# SparkFun_9DoF_ISM330DHCX-MMC5983MA.net
KiCad netlist of a schematic drawn in EAGLE
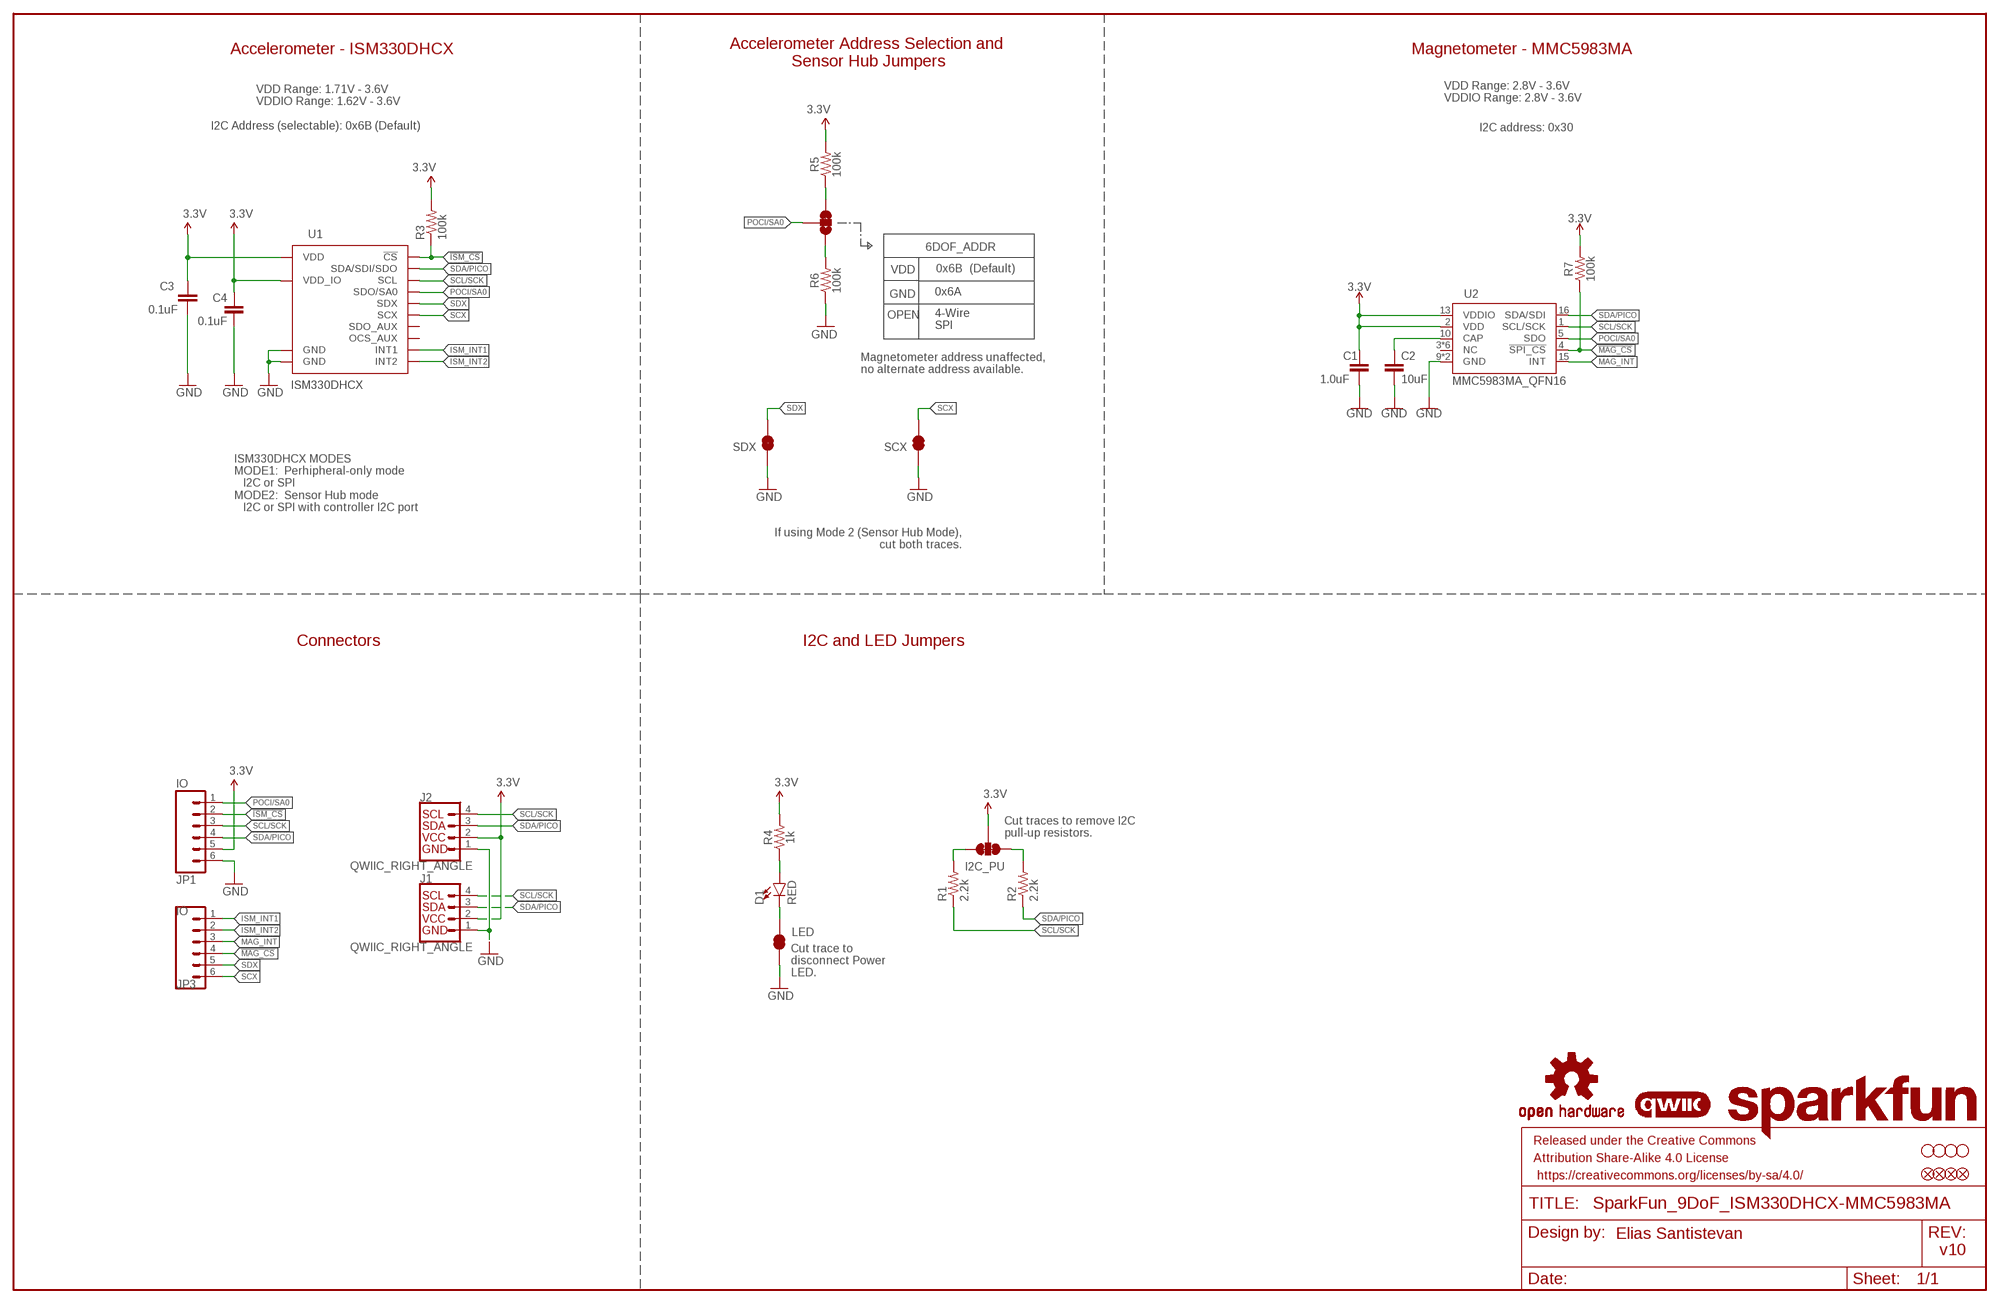
[diagram p0: schematic, sheet 1]

(export (version "E")
  (design (tool "Eeschema 10.0.6"))
  (components
    (comp (ref "6DOF_ADDR")
      (value "JUMPER-SMT_3_1-NC_TRACE_SILK")
      (footprint "eagle-import:SMT-JUMPER_3_1-NC_TRACE_SILK")
      (libsource (lib "eagle-import") (part "JUMPER-SMT_3_1-NC_TRACE_SILK"))
    )
    (comp (ref "C1")
      (value "1.0uF")
      (footprint "eagle-import:0603")
      (libsource (lib "eagle-import") (part "1.0UF-0603-16V-10%"))
    )
    (comp (ref "C2")
      (value "10uF")
      (footprint "eagle-import:0603")
      (libsource (lib "eagle-import") (part "10UF-0603-6.3V-20%"))
    )
    (comp (ref "C3")
      (value "0.1uF")
      (footprint "eagle-import:0603")
      (libsource (lib "eagle-import") (part "0.1UF-0603-25V-(+80/-20%)"))
    )
    (comp (ref "C4")
      (value "0.1uF")
      (footprint "eagle-import:0603")
      (libsource (lib "eagle-import") (part "0.1UF-0603-25V-(+80/-20%)"))
    )
    (comp (ref "D1")
      (value "RED")
      (footprint "eagle-import:LED-0603")
      (libsource (lib "eagle-import") (part "LED-RED0603"))
    )
    (comp (ref "FD1")
      (value "FIDUCIALUFIDUCIAL")
      (footprint "eagle-import:FIDUCIAL-MICRO")
      (libsource (lib "eagle-import") (part "FIDUCIALUFIDUCIAL"))
    )
    (comp (ref "FD2")
      (value "FIDUCIALUFIDUCIAL")
      (footprint "eagle-import:FIDUCIAL-MICRO")
      (libsource (lib "eagle-import") (part "FIDUCIALUFIDUCIAL"))
    )
    (comp (ref "FID1")
      (value "FIDUCIALUFIDUCIAL")
      (footprint "eagle-import:FIDUCIAL-MICRO")
      (libsource (lib "eagle-import") (part "FIDUCIALUFIDUCIAL"))
    )
    (comp (ref "FID2")
      (value "FIDUCIALUFIDUCIAL")
      (footprint "eagle-import:FIDUCIAL-MICRO")
      (libsource (lib "eagle-import") (part "FIDUCIALUFIDUCIAL"))
    )
    (comp (ref "FRAME2")
      (value "FRAME-LEDGER")
      (footprint "eagle-import:CREATIVE_COMMONS")
      (libsource (lib "eagle-import") (part "FRAME-LEDGER"))
    )
    (comp (ref "I2C_PU")
      (value "S_MODE")
      (footprint "eagle-import:SMT-JUMPER_3_2-NC_TRACE_SILK")
      (libsource (lib "eagle-import") (part "JUMPER-SMT_3_2-NC_TRACE_SILK"))
    )
    (comp (ref "J1")
      (value "QWIIC_RIGHT_ANGLE")
      (footprint "eagle-import:JST04_1MM_RA")
      (libsource (lib "eagle-import") (part "QWIIC_CONNECTORJS-1MM"))
    )
    (comp (ref "J2")
      (value "QWIIC_RIGHT_ANGLE")
      (footprint "eagle-import:JST04_1MM_RA")
      (libsource (lib "eagle-import") (part "QWIIC_CONNECTORJS-1MM"))
    )
    (comp (ref "JP1")
      (value "IO")
      (footprint "eagle-import:1X06_NO_SILK")
      (libsource (lib "eagle-import") (part "CONN_06NO_SILK_NO_POP"))
    )
    (comp (ref "JP3")
      (value "IO")
      (footprint "eagle-import:1X06_NO_SILK")
      (libsource (lib "eagle-import") (part "CONN_06NO_SILK_NO_POP"))
    )
    (comp (ref "LED")
      (value "JUMPER-SMT_2_NC_TRACE_SILK")
      (footprint "eagle-import:SMT-JUMPER_2_NC_TRACE_SILK")
      (libsource (lib "eagle-import") (part "JUMPER-SMT_2_NC_TRACE_SILK"))
    )
    (comp (ref "LOGO1")
      (value "QWIIC_LOGO_4MM")
      (footprint "eagle-import:QWIIC_4MM")
      (libsource (lib "eagle-import") (part "QWIIC_LOGO_4MM"))
    )
    (comp (ref "LOGO2")
      (value "OSHW-LOGOMINI")
      (footprint "eagle-import:OSHW-LOGO-MINI")
      (libsource (lib "eagle-import") (part "OSHW-LOGOMINI"))
    )
    (comp (ref "LOGO3")
      (value "SFE_LOGO_NAME.1_INCH")
      (footprint "eagle-import:SFE_LOGO_NAME_.1")
      (libsource (lib "eagle-import") (part "SFE_LOGO_NAME.1_INCH"))
    )
    (comp (ref "R1")
      (value "2.2k")
      (footprint "eagle-import:0603")
      (libsource (lib "eagle-import") (part "2.2KOHM-0603-1/10W-1%"))
    )
    (comp (ref "R2")
      (value "2.2k")
      (footprint "eagle-import:0603")
      (libsource (lib "eagle-import") (part "2.2KOHM-0603-1/10W-1%"))
    )
    (comp (ref "R3")
      (value "100k")
      (footprint "eagle-import:0603")
      (libsource (lib "eagle-import") (part "100KOHM-0603-1/10W-1%"))
    )
    (comp (ref "R4")
      (value "1k")
      (footprint "eagle-import:0603")
      (libsource (lib "eagle-import") (part "1KOHM-0603-1/10W-1%"))
    )
    (comp (ref "R5")
      (value "100k")
      (footprint "eagle-import:0603")
      (libsource (lib "eagle-import") (part "100KOHM-0603-1/10W-1%"))
    )
    (comp (ref "R6")
      (value "100k")
      (footprint "eagle-import:0603")
      (libsource (lib "eagle-import") (part "100KOHM-0603-1/10W-1%"))
    )
    (comp (ref "R7")
      (value "100k")
      (footprint "eagle-import:0603")
      (libsource (lib "eagle-import") (part "100KOHM-0603-1/10W-1%"))
    )
    (comp (ref "SCX")
      (value "JUMPER-SMT_2_NC_TRACE_SILK")
      (footprint "eagle-import:SMT-JUMPER_2_NC_TRACE_SILK")
      (libsource (lib "eagle-import") (part "JUMPER-SMT_2_NC_TRACE_SILK"))
    )
    (comp (ref "SDX")
      (value "JUMPER-SMT_2_NC_TRACE_SILK")
      (footprint "eagle-import:SMT-JUMPER_2_NC_TRACE_SILK")
      (libsource (lib "eagle-import") (part "JUMPER-SMT_2_NC_TRACE_SILK"))
    )
    (comp (ref "STANDOFF1")
      (value "STAND-OFFTIGHT")
      (footprint "eagle-import:STAND-OFF-TIGHT")
      (libsource (lib "eagle-import") (part "STAND-OFFTIGHT"))
    )
    (comp (ref "STANDOFF2")
      (value "STAND-OFFTIGHT")
      (footprint "eagle-import:STAND-OFF-TIGHT")
      (libsource (lib "eagle-import") (part "STAND-OFFTIGHT"))
    )
    (comp (ref "STANDOFF3")
      (value "STAND-OFFTIGHT")
      (footprint "eagle-import:STAND-OFF-TIGHT")
      (libsource (lib "eagle-import") (part "STAND-OFFTIGHT"))
    )
    (comp (ref "STANDOFF4")
      (value "STAND-OFFTIGHT")
      (footprint "eagle-import:STAND-OFF-TIGHT")
      (libsource (lib "eagle-import") (part "STAND-OFFTIGHT"))
    )
    (comp (ref "U1")
      (value "ISM330DHCX")
      (footprint "eagle-import:LGA-14L")
      (libsource (lib "eagle-import") (part "ISM330DHCX"))
    )
    (comp (ref "U2")
      (value "MMC5983MA_QFN16")
      (footprint "eagle-import:LGA-16-3X3MM-4X4PINS")
      (libsource (lib "eagle-import") (part "MMC5983MA_QFN16"))
    )
  )
  (nets
    (net (code "1") (name "/~{ISM_CS}") (class "Default")
      (node (ref "JP1") (pin "2") (pinfunction "2_2") (pintype "passive"))
      (node (ref "R3") (pin "1") (pinfunction "1_1") (pintype "passive"))
      (node (ref "U1") (pin "P12") (pinfunction "~{CS}_P12") (pintype "bidirectional"))
    )
    (net (code "2") (name "/~{MAG_CS}") (class "Default")
      (node (ref "JP3") (pin "4") (pinfunction "4_4") (pintype "passive"))
      (node (ref "R7") (pin "1") (pinfunction "1_1") (pintype "passive"))
      (node (ref "U2") (pin "4") (pinfunction "~{SPI_CS}_4") (pintype "input"))
    )
    (net (code "3") (name "3.3V") (class "Default")
      (node (ref "C1") (pin "1") (pinfunction "1_1") (pintype "passive"))
      (node (ref "C3") (pin "1") (pinfunction "1_1") (pintype "passive"))
      (node (ref "C4") (pin "1") (pinfunction "1_1") (pintype "passive"))
      (node (ref "I2C_PU") (pin "2") (pinfunction "2_2") (pintype "passive"))
      (node (ref "J1") (pin "2") (pinfunction "2_2") (pintype "power_in"))
      (node (ref "J2") (pin "2") (pinfunction "2_2") (pintype "power_in"))
      (node (ref "JP1") (pin "5") (pinfunction "5_5") (pintype "passive"))
      (node (ref "R3") (pin "2") (pinfunction "2_2") (pintype "passive"))
      (node (ref "R4") (pin "2") (pinfunction "2_2") (pintype "passive"))
      (node (ref "R5") (pin "2") (pinfunction "2_2") (pintype "passive"))
      (node (ref "R7") (pin "2") (pinfunction "2_2") (pintype "passive"))
      (node (ref "U1") (pin "P5") (pinfunction "VDD_IO_P5") (pintype "power_in"))
      (node (ref "U1") (pin "P8") (pinfunction "VDD_P8") (pintype "power_in"))
      (node (ref "U2") (pin "13") (pinfunction "VDDIO_13") (pintype "power_in"))
      (node (ref "U2") (pin "2") (pinfunction "VDD_2") (pintype "power_in"))
    )
    (net (code "4") (name "GND") (class "Default")
      (node (ref "C1") (pin "2") (pinfunction "2_2") (pintype "passive"))
      (node (ref "C2") (pin "2") (pinfunction "2_2") (pintype "passive"))
      (node (ref "C3") (pin "2") (pinfunction "2_2") (pintype "passive"))
      (node (ref "C4") (pin "2") (pinfunction "2_2") (pintype "passive"))
      (node (ref "J1") (pin "1") (pinfunction "1_1") (pintype "power_in"))
      (node (ref "J2") (pin "1") (pinfunction "1_1") (pintype "power_in"))
      (node (ref "JP1") (pin "6") (pinfunction "6_6") (pintype "passive"))
      (node (ref "LED") (pin "1") (pinfunction "1_1") (pintype "passive"))
      (node (ref "R6") (pin "1") (pinfunction "1_1") (pintype "passive"))
      (node (ref "SCX") (pin "1") (pinfunction "1_1") (pintype "passive"))
      (node (ref "SDX") (pin "1") (pinfunction "1_1") (pintype "passive"))
      (node (ref "U1") (pin "P6") (pinfunction "GND_P6") (pintype "power_in"))
      (node (ref "U1") (pin "P7") (pinfunction "GND_P7") (pintype "power_in"))
      (node (ref "U2") (pin "11") (pinfunction "GND_11") (pintype "power_in"))
      (node (ref "U2") (pin "9") (pinfunction "GND_9") (pintype "power_in"))
    )
    (net (code "5") (name "ISM_INT1") (class "Default")
      (node (ref "JP3") (pin "1") (pinfunction "1_1") (pintype "passive"))
      (node (ref "U1") (pin "P4") (pinfunction "INT1_P4") (pintype "bidirectional"))
    )
    (net (code "6") (name "ISM_INT2") (class "Default")
      (node (ref "JP3") (pin "2") (pinfunction "2_2") (pintype "passive"))
      (node (ref "U1") (pin "P9") (pinfunction "INT2_P9") (pintype "bidirectional"))
    )
    (net (code "7") (name "MAG_INT") (class "Default")
      (node (ref "JP3") (pin "3") (pinfunction "3_3") (pintype "passive"))
      (node (ref "U2") (pin "15") (pinfunction "INT_15") (pintype "output"))
    )
    (net (code "8") (name "Net-(6DOF_ADDR-Pad1)") (class "Default")
      (node (ref "6DOF_ADDR") (pin "1") (pinfunction "1_1") (pintype "passive"))
      (node (ref "R6") (pin "2") (pinfunction "2_2") (pintype "passive"))
    )
    (net (code "9") (name "Net-(6DOF_ADDR-Pad3)") (class "Default")
      (node (ref "6DOF_ADDR") (pin "3") (pinfunction "3_3") (pintype "passive"))
      (node (ref "R5") (pin "1") (pinfunction "1_1") (pintype "passive"))
    )
    (net (code "10") (name "Net-(D1-PadA)") (class "Default")
      (node (ref "D1") (pin "A") (pinfunction "A_A") (pintype "passive"))
      (node (ref "R4") (pin "1") (pinfunction "1_1") (pintype "passive"))
    )
    (net (code "11") (name "Net-(D1-PadC)") (class "Default")
      (node (ref "D1") (pin "C") (pinfunction "C_C") (pintype "passive"))
      (node (ref "LED") (pin "2") (pinfunction "2_2") (pintype "passive"))
    )
    (net (code "12") (name "Net-(I2C_PU-Pad1)") (class "Default")
      (node (ref "I2C_PU") (pin "1") (pinfunction "1_1") (pintype "passive"))
      (node (ref "R1") (pin "2") (pinfunction "2_2") (pintype "passive"))
    )
    (net (code "13") (name "Net-(I2C_PU-Pad3)") (class "Default")
      (node (ref "I2C_PU") (pin "3") (pinfunction "3_3") (pintype "passive"))
      (node (ref "R2") (pin "2") (pinfunction "2_2") (pintype "passive"))
    )
    (net (code "14") (name "Net-(U2-CAP)") (class "Default")
      (node (ref "C2") (pin "1") (pinfunction "1_1") (pintype "passive"))
      (node (ref "U2") (pin "10") (pinfunction "CAP_10") (pintype "passive"))
    )
    (net (code "15") (name "POCI{slash}SA0") (class "Default")
      (node (ref "6DOF_ADDR") (pin "2") (pinfunction "2_2") (pintype "passive"))
      (node (ref "JP1") (pin "1") (pinfunction "1_1") (pintype "passive"))
      (node (ref "U1") (pin "P1") (pinfunction "SDO/SA0_P1") (pintype "bidirectional"))
      (node (ref "U2") (pin "5") (pinfunction "SDO_5") (pintype "output"))
    )
    (net (code "16") (name "SCL{slash}SCK") (class "Default")
      (node (ref "J1") (pin "4") (pinfunction "4_4") (pintype "passive"))
      (node (ref "J2") (pin "4") (pinfunction "4_4") (pintype "passive"))
      (node (ref "JP1") (pin "3") (pinfunction "3_3") (pintype "passive"))
      (node (ref "R1") (pin "1") (pinfunction "1_1") (pintype "passive"))
      (node (ref "U1") (pin "P13") (pinfunction "SCL_P13") (pintype "bidirectional"))
      (node (ref "U2") (pin "1") (pinfunction "SCL/SCK_1") (pintype "bidirectional"))
    )
    (net (code "17") (name "SCX") (class "Default")
      (node (ref "JP3") (pin "6") (pinfunction "6_6") (pintype "passive"))
      (node (ref "SCX") (pin "2") (pinfunction "2_2") (pintype "passive"))
      (node (ref "U1") (pin "P3") (pinfunction "SCX_P3") (pintype "bidirectional"))
    )
    (net (code "18") (name "SDA{slash}PICO") (class "Default")
      (node (ref "J1") (pin "3") (pinfunction "3_3") (pintype "passive"))
      (node (ref "J2") (pin "3") (pinfunction "3_3") (pintype "passive"))
      (node (ref "JP1") (pin "4") (pinfunction "4_4") (pintype "passive"))
      (node (ref "R2") (pin "1") (pinfunction "1_1") (pintype "passive"))
      (node (ref "U1") (pin "P14") (pinfunction "SDA/SDI/SDO_P14") (pintype "bidirectional"))
      (node (ref "U2") (pin "16") (pinfunction "SDA/SDI_16") (pintype "bidirectional"))
    )
    (net (code "19") (name "SDX") (class "Default")
      (node (ref "JP3") (pin "5") (pinfunction "5_5") (pintype "passive"))
      (node (ref "SDX") (pin "2") (pinfunction "2_2") (pintype "passive"))
      (node (ref "U1") (pin "P2") (pinfunction "SDX_P2") (pintype "bidirectional"))
    )
    (net (code "20") (name "unconnected-(U1-OCS_AUX-PadP10)") (class "Default")
      (node (ref "U1") (pin "P10") (pinfunction "OCS_AUX_P10") (pintype "bidirectional"))
    )
    (net (code "21") (name "unconnected-(U1-SDO_AUX-PadP11)") (class "Default")
      (node (ref "U1") (pin "P11") (pinfunction "SDO_AUX_P11") (pintype "bidirectional"))
    )
    (net (code "22") (name "unconnected-(U2-NC-Pad3)") (class "Default")
      (node (ref "U2") (pin "3") (pinfunction "NC_3") (pintype "no_connect"))
    )
    (net (code "23") (name "unconnected-(U2-NC-Pad6)") (class "Default")
      (node (ref "U2") (pin "6") (pinfunction "NC_6") (pintype "no_connect"))
    )
    (net (code "24") (name "unconnected-(U2-NC-Pad7)") (class "Default")
      (node (ref "U2") (pin "7") (pinfunction "NC_7") (pintype "no_connect"))
    )
    (net (code "25") (name "unconnected-(U2-NC-Pad8)") (class "Default")
      (node (ref "U2") (pin "8") (pinfunction "NC_8") (pintype "no_connect"))
    )
    (net (code "26") (name "unconnected-(U2-NC-Pad12)") (class "Default")
      (node (ref "U2") (pin "12") (pinfunction "NC_12") (pintype "no_connect"))
    )
    (net (code "27") (name "unconnected-(U2-NC-Pad14)") (class "Default")
      (node (ref "U2") (pin "14") (pinfunction "NC_14") (pintype "no_connect"))
    )
  )
)
